# usbc-plug-test.net
KiCad netlist of a schematic drawn in EAGLE
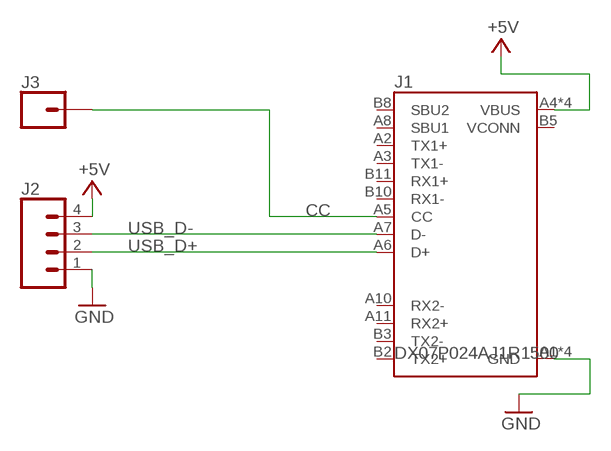
[diagram p0: schematic, sheet 1]

(export (version "E")
  (design (tool "Eeschema 10.0.6"))
  (components
    (comp (ref "J1")
      (value "DX07P024AJ1R1500")
      (footprint "eagle-import:JAE_DX07P024AJ1R1500")
      (fields (field (name "DIGI-KEY_PART_NUMBER") "670-2868-1-ND") (field (name "MF") "JAE Electronics"))
      (libsource (lib "eagle-import") (part "DX07P024AJ1R1500"))
    )
    (comp (ref "J2")
      (value "CONN_04")
      (footprint "eagle-import:1X04")
      (libsource (lib "eagle-import") (part "CONN_04"))
    )
    (comp (ref "J3")
      (value "CONN_01")
      (footprint "eagle-import:1X01")
      (libsource (lib "eagle-import") (part "CONN_01"))
    )
  )
  (nets
    (net (code "1") (name "+5V") (class "Default")
      (node (ref "J1") (pin "A4") (pinfunction "VBUS_A4") (pintype "power_in"))
      (node (ref "J1") (pin "A9") (pinfunction "VBUS_A9") (pintype "power_in"))
      (node (ref "J1") (pin "B4") (pinfunction "VBUS_B4") (pintype "power_in"))
      (node (ref "J1") (pin "B9") (pinfunction "VBUS_B9") (pintype "power_in"))
      (node (ref "J2") (pin "4") (pinfunction "4_4") (pintype "passive"))
    )
    (net (code "2") (name "/CC") (class "Default")
      (node (ref "J1") (pin "A5") (pinfunction "CC_A5") (pintype "bidirectional"))
      (node (ref "J3") (pin "1") (pinfunction "1_1") (pintype "passive"))
    )
    (net (code "3") (name "/USB_D+") (class "Default")
      (node (ref "J1") (pin "A6") (pinfunction "D+_A6") (pintype "bidirectional"))
      (node (ref "J2") (pin "2") (pinfunction "2_2") (pintype "passive"))
    )
    (net (code "4") (name "/USB_D-") (class "Default")
      (node (ref "J1") (pin "A7") (pinfunction "D-_A7") (pintype "bidirectional"))
      (node (ref "J2") (pin "3") (pinfunction "3_3") (pintype "passive"))
    )
    (net (code "5") (name "/VCONN") (class "Default")
      (node (ref "J1") (pin "B5") (pinfunction "VCONN_B5") (pintype "power_in"))
    )
    (net (code "6") (name "GND") (class "Default")
      (node (ref "J1") (pin "A1") (pinfunction "GND_A1") (pintype "power_in"))
      (node (ref "J1") (pin "A12") (pinfunction "GND_A12") (pintype "power_in"))
      (node (ref "J1") (pin "B1") (pinfunction "GND_B1") (pintype "power_in"))
      (node (ref "J1") (pin "B12") (pinfunction "GND_B12") (pintype "power_in"))
      (node (ref "J2") (pin "1") (pinfunction "1_1") (pintype "passive"))
    )
    (net (code "7") (name "unconnected-(J1-RX1+-PadB11)") (class "Default")
      (node (ref "J1") (pin "B11") (pinfunction "RX1+_B11") (pintype "bidirectional"))
    )
    (net (code "8") (name "unconnected-(J1-RX1--PadB10)") (class "Default")
      (node (ref "J1") (pin "B10") (pinfunction "RX1-_B10") (pintype "bidirectional"))
    )
    (net (code "9") (name "unconnected-(J1-RX2+-PadA11)") (class "Default")
      (node (ref "J1") (pin "A11") (pinfunction "RX2+_A11") (pintype "bidirectional"))
    )
    (net (code "10") (name "unconnected-(J1-RX2--PadA10)") (class "Default")
      (node (ref "J1") (pin "A10") (pinfunction "RX2-_A10") (pintype "bidirectional"))
    )
    (net (code "11") (name "unconnected-(J1-SBU1-PadA8)") (class "Default")
      (node (ref "J1") (pin "A8") (pinfunction "SBU1_A8") (pintype "bidirectional"))
    )
    (net (code "12") (name "unconnected-(J1-SBU2-PadB8)") (class "Default")
      (node (ref "J1") (pin "B8") (pinfunction "SBU2_B8") (pintype "bidirectional"))
    )
    (net (code "13") (name "unconnected-(J1-TX1+-PadA2)") (class "Default")
      (node (ref "J1") (pin "A2") (pinfunction "TX1+_A2") (pintype "bidirectional"))
    )
    (net (code "14") (name "unconnected-(J1-TX1--PadA3)") (class "Default")
      (node (ref "J1") (pin "A3") (pinfunction "TX1-_A3") (pintype "bidirectional"))
    )
    (net (code "15") (name "unconnected-(J1-TX2+-PadB2)") (class "Default")
      (node (ref "J1") (pin "B2") (pinfunction "TX2+_B2") (pintype "bidirectional"))
    )
    (net (code "16") (name "unconnected-(J1-TX2--PadB3)") (class "Default")
      (node (ref "J1") (pin "B3") (pinfunction "TX2-_B3") (pintype "bidirectional"))
    )
  )
)
